# MADpassLightV2.net
KiCad netlist of a schematic drawn in EAGLE
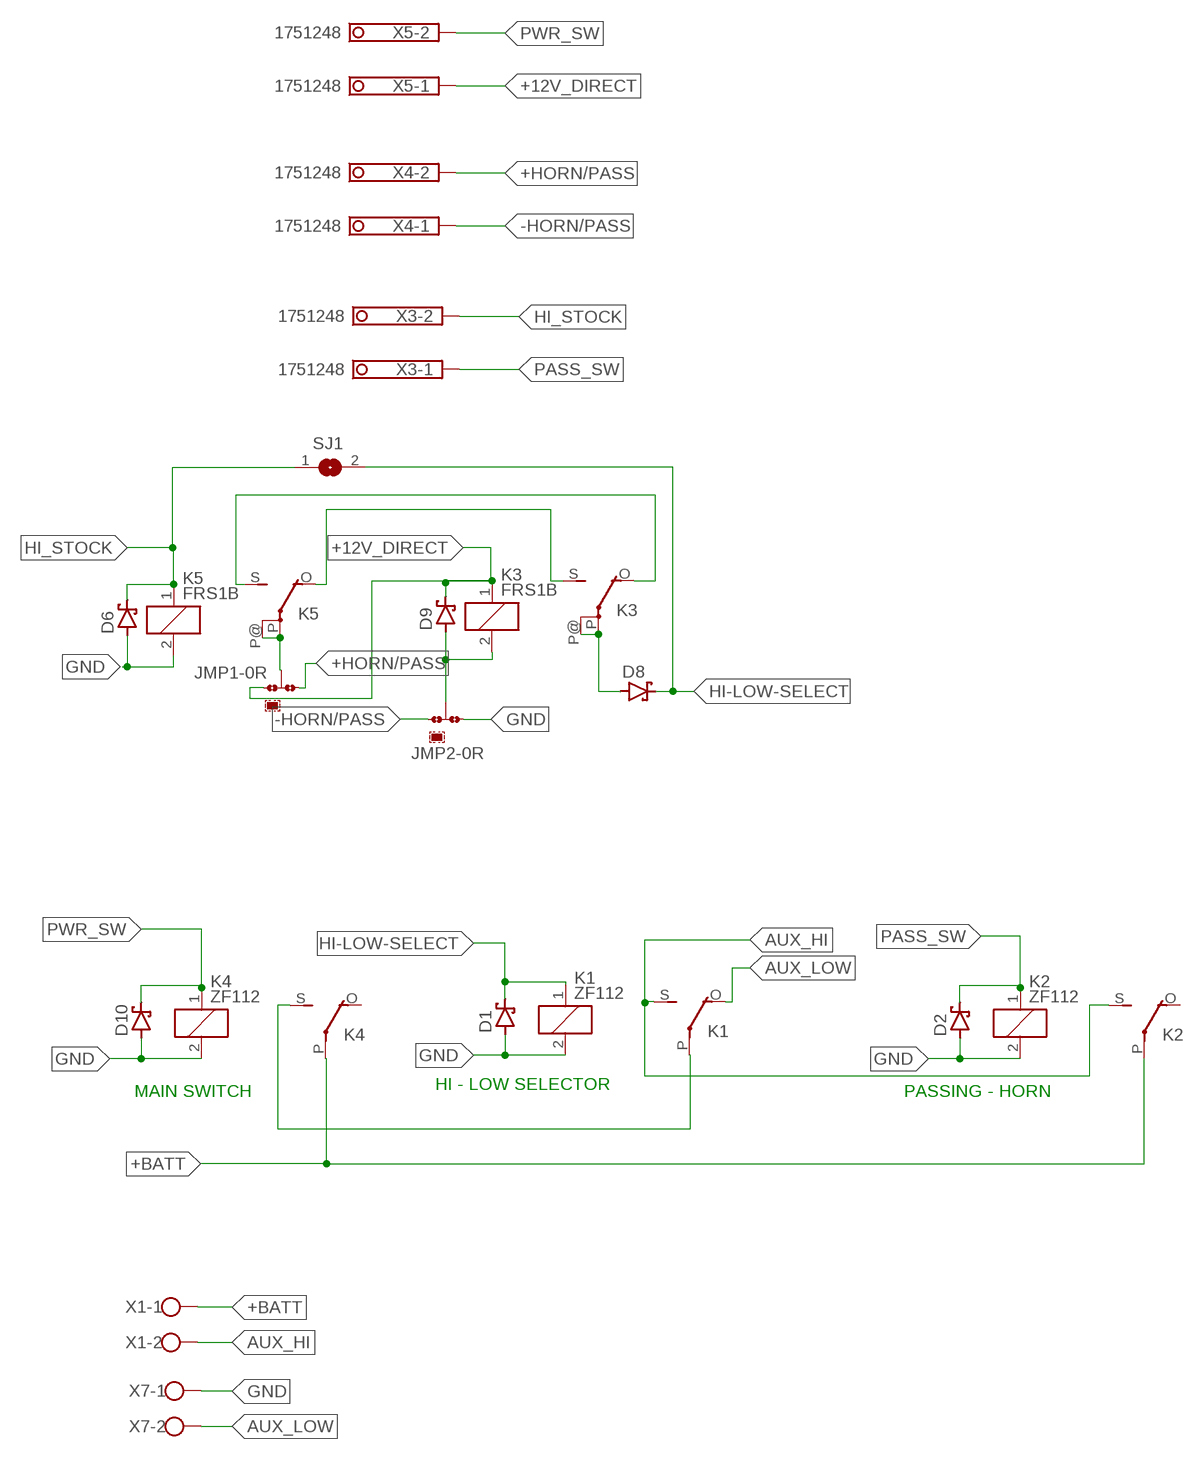
[diagram p0: schematic, sheet 1]

(export (version "E")
  (design (tool "Eeschema 10.0.6"))
  (components
    (comp (ref "D1")
      (value "SCHOTTKY-DIODESMD")
      (footprint "eagle-import:SMB")
      (libsource (lib "eagle-import") (part "SCHOTTKY-DIODESMD"))
    )
    (comp (ref "D2")
      (value "SCHOTTKY-DIODESMD")
      (footprint "eagle-import:SMB")
      (libsource (lib "eagle-import") (part "SCHOTTKY-DIODESMD"))
    )
    (comp (ref "D6")
      (value "SCHOTTKY-DIODESMD")
      (footprint "eagle-import:SMB")
      (libsource (lib "eagle-import") (part "SCHOTTKY-DIODESMD"))
    )
    (comp (ref "D8")
      (value "SCHOTTKY-DIODESMD")
      (footprint "eagle-import:SMB")
      (libsource (lib "eagle-import") (part "SCHOTTKY-DIODESMD"))
    )
    (comp (ref "D9")
      (value "SCHOTTKY-DIODESMD")
      (footprint "eagle-import:SMB")
      (libsource (lib "eagle-import") (part "SCHOTTKY-DIODESMD"))
    )
    (comp (ref "D10")
      (value "SCHOTTKY-DIODESMD")
      (footprint "eagle-import:SMB")
      (libsource (lib "eagle-import") (part "SCHOTTKY-DIODESMD"))
    )
    (comp (ref "JMP1")
      (value "0R-JUMPA")
      (footprint "eagle-import:A0R-JMP")
      (libsource (lib "eagle-import") (part "0R-JUMPA"))
    )
    (comp (ref "JMP2")
      (value "0R-JUMPA")
      (footprint "eagle-import:A0R-JMP")
      (libsource (lib "eagle-import") (part "0R-JUMPA"))
    )
    (comp (ref "K1")
      (value "ZF112")
      (footprint "eagle-import:ZF112")
      (libsource (lib "eagle-import") (part "ZF112"))
    )
    (comp (ref "K2")
      (value "ZF112")
      (footprint "eagle-import:ZF112")
      (libsource (lib "eagle-import") (part "ZF112"))
    )
    (comp (ref "K3")
      (value "FRS1B")
      (footprint "eagle-import:FRS1B")
      (libsource (lib "eagle-import") (part "FRS1B"))
    )
    (comp (ref "K4")
      (value "ZF112")
      (footprint "eagle-import:ZF112")
      (libsource (lib "eagle-import") (part "ZF112"))
    )
    (comp (ref "K5")
      (value "FRS1B")
      (footprint "eagle-import:FRS1B")
      (libsource (lib "eagle-import") (part "FRS1B"))
    )
    (comp (ref "SJ1") (value "SJ") (footprint "eagle-import:SJ") (libsource (lib "eagle-import") (part "SJ")))
    (comp (ref "X1")
      (value "W237-102")
      (footprint "eagle-import:W237-102")
      (fields (field (name "MPN") "237-102"))
      (libsource (lib "eagle-import") (part "W237-102"))
    )
    (comp (ref "X3")
      (value "1751248")
      (footprint "eagle-import:1751248")
      (libsource (lib "eagle-import") (part "1751248"))
    )
    (comp (ref "X4")
      (value "1751248")
      (footprint "eagle-import:1751248")
      (libsource (lib "eagle-import") (part "1751248"))
    )
    (comp (ref "X5")
      (value "1751248")
      (footprint "eagle-import:1751248")
      (libsource (lib "eagle-import") (part "1751248"))
    )
    (comp (ref "X7")
      (value "W237-102")
      (footprint "eagle-import:W237-102")
      (fields (field (name "MPN") "237-102"))
      (libsource (lib "eagle-import") (part "W237-102"))
    )
  )
  (nets
    (net (code "1") (name "+12V_DIRECT") (class "Default")
      (node (ref "D9") (pin "C") (pinfunction "C_C") (pintype "passive"))
      (node (ref "JMP1") (pin "1") (pinfunction "1_1") (pintype "passive"))
      (node (ref "K3") (pin "1") (pinfunction "1_1") (pintype "passive"))
      (node (ref "X5") (pin "1") (pinfunction "K_1") (pintype "passive"))
    )
    (net (code "2") (name "+BATT") (class "Default")
      (node (ref "K2") (pin "P") (pinfunction "P_P") (pintype "passive"))
      (node (ref "K4") (pin "P") (pinfunction "P_P") (pintype "passive"))
      (node (ref "X1") (pin "1") (pinfunction "KL_1") (pintype "passive"))
    )
    (net (code "3") (name "+HORN{slash}PASS") (class "Default")
      (node (ref "JMP1") (pin "3") (pinfunction "3_3") (pintype "passive"))
      (node (ref "X4") (pin "2") (pinfunction "K_2") (pintype "passive"))
    )
    (net (code "4") (name "-HORN{slash}PASS") (class "Default")
      (node (ref "JMP2") (pin "1") (pinfunction "1_1") (pintype "passive"))
      (node (ref "X4") (pin "1") (pinfunction "K_1") (pintype "passive"))
    )
    (net (code "5") (name "AUX_HI") (class "Default")
      (node (ref "K1") (pin "S") (pinfunction "S_S") (pintype "passive"))
      (node (ref "K2") (pin "S") (pinfunction "S_S") (pintype "passive"))
      (node (ref "X1") (pin "2") (pinfunction "KL_2") (pintype "passive"))
    )
    (net (code "6") (name "AUX_LOW") (class "Default")
      (node (ref "K1") (pin "O") (pinfunction "O_O") (pintype "passive"))
      (node (ref "X7") (pin "2") (pinfunction "KL_2") (pintype "passive"))
    )
    (net (code "7") (name "GND") (class "Default")
      (node (ref "D1") (pin "A") (pinfunction "A_A") (pintype "passive"))
      (node (ref "D10") (pin "A") (pinfunction "A_A") (pintype "passive"))
      (node (ref "D2") (pin "A") (pinfunction "A_A") (pintype "passive"))
      (node (ref "D6") (pin "A") (pinfunction "A_A") (pintype "passive"))
      (node (ref "JMP2") (pin "3") (pinfunction "3_3") (pintype "passive"))
      (node (ref "K1") (pin "2") (pinfunction "2_2") (pintype "passive"))
      (node (ref "K2") (pin "2") (pinfunction "2_2") (pintype "passive"))
      (node (ref "K4") (pin "2") (pinfunction "2_2") (pintype "passive"))
      (node (ref "K5") (pin "2") (pinfunction "2_2") (pintype "passive"))
      (node (ref "X7") (pin "1") (pinfunction "KL_1") (pintype "passive"))
    )
    (net (code "8") (name "HI-LOW-SELECT") (class "Default")
      (node (ref "D1") (pin "C") (pinfunction "C_C") (pintype "passive"))
      (node (ref "D8") (pin "C") (pinfunction "C_C") (pintype "passive"))
      (node (ref "K1") (pin "1") (pinfunction "1_1") (pintype "passive"))
      (node (ref "SJ1") (pin "2") (pinfunction "2_2") (pintype "passive"))
    )
    (net (code "9") (name "HI_STOCK") (class "Default")
      (node (ref "D6") (pin "C") (pinfunction "C_C") (pintype "passive"))
      (node (ref "K5") (pin "1") (pinfunction "1_1") (pintype "passive"))
      (node (ref "SJ1") (pin "1") (pinfunction "1_1") (pintype "passive"))
      (node (ref "X3") (pin "2") (pinfunction "K_2") (pintype "passive"))
    )
    (net (code "10") (name "Net-(D8-PadA)") (class "Default")
      (node (ref "D8") (pin "A") (pinfunction "A_A") (pintype "passive"))
      (node (ref "K3") (pin "P") (pinfunction "P_P") (pintype "passive"))
      (node (ref "K3") (pin "P@") (pinfunction "P_P@") (pintype "passive"))
    )
    (net (code "11") (name "Net-(D9-PadA)") (class "Default")
      (node (ref "D9") (pin "A") (pinfunction "A_A") (pintype "passive"))
      (node (ref "JMP2") (pin "2") (pinfunction "2_2") (pintype "passive"))
      (node (ref "K3") (pin "2") (pinfunction "2_2") (pintype "passive"))
    )
    (net (code "12") (name "Net-(JMP1-Pad2)") (class "Default")
      (node (ref "JMP1") (pin "2") (pinfunction "2_2") (pintype "passive"))
      (node (ref "K5") (pin "P") (pinfunction "P_P") (pintype "passive"))
      (node (ref "K5") (pin "P@") (pinfunction "P_P@") (pintype "passive"))
    )
    (net (code "13") (name "Net-(K1-PadP)") (class "Default")
      (node (ref "K1") (pin "P") (pinfunction "P_P") (pintype "passive"))
      (node (ref "K4") (pin "S") (pinfunction "S_S") (pintype "passive"))
    )
    (net (code "14") (name "Net-(K3-PadO)") (class "Default")
      (node (ref "K3") (pin "O") (pinfunction "O_O") (pintype "passive"))
      (node (ref "K5") (pin "S") (pinfunction "S_S") (pintype "passive"))
    )
    (net (code "15") (name "Net-(K3-PadS)") (class "Default")
      (node (ref "K3") (pin "S") (pinfunction "S_S") (pintype "passive"))
      (node (ref "K5") (pin "O") (pinfunction "O_O") (pintype "passive"))
    )
    (net (code "16") (name "PASS_SW") (class "Default")
      (node (ref "D2") (pin "C") (pinfunction "C_C") (pintype "passive"))
      (node (ref "K2") (pin "1") (pinfunction "1_1") (pintype "passive"))
      (node (ref "X3") (pin "1") (pinfunction "K_1") (pintype "passive"))
    )
    (net (code "17") (name "PWR_SW") (class "Default")
      (node (ref "D10") (pin "C") (pinfunction "C_C") (pintype "passive"))
      (node (ref "K4") (pin "1") (pinfunction "1_1") (pintype "passive"))
      (node (ref "X5") (pin "2") (pinfunction "K_2") (pintype "passive"))
    )
    (net (code "18") (name "unconnected-(K2-PadO)") (class "Default")
      (node (ref "K2") (pin "O") (pinfunction "O_O") (pintype "passive"))
    )
    (net (code "19") (name "unconnected-(K4-PadO)") (class "Default")
      (node (ref "K4") (pin "O") (pinfunction "O_O") (pintype "passive"))
    )
  )
)
